# main.net
KiCad netlist of a schematic drawn in EAGLE
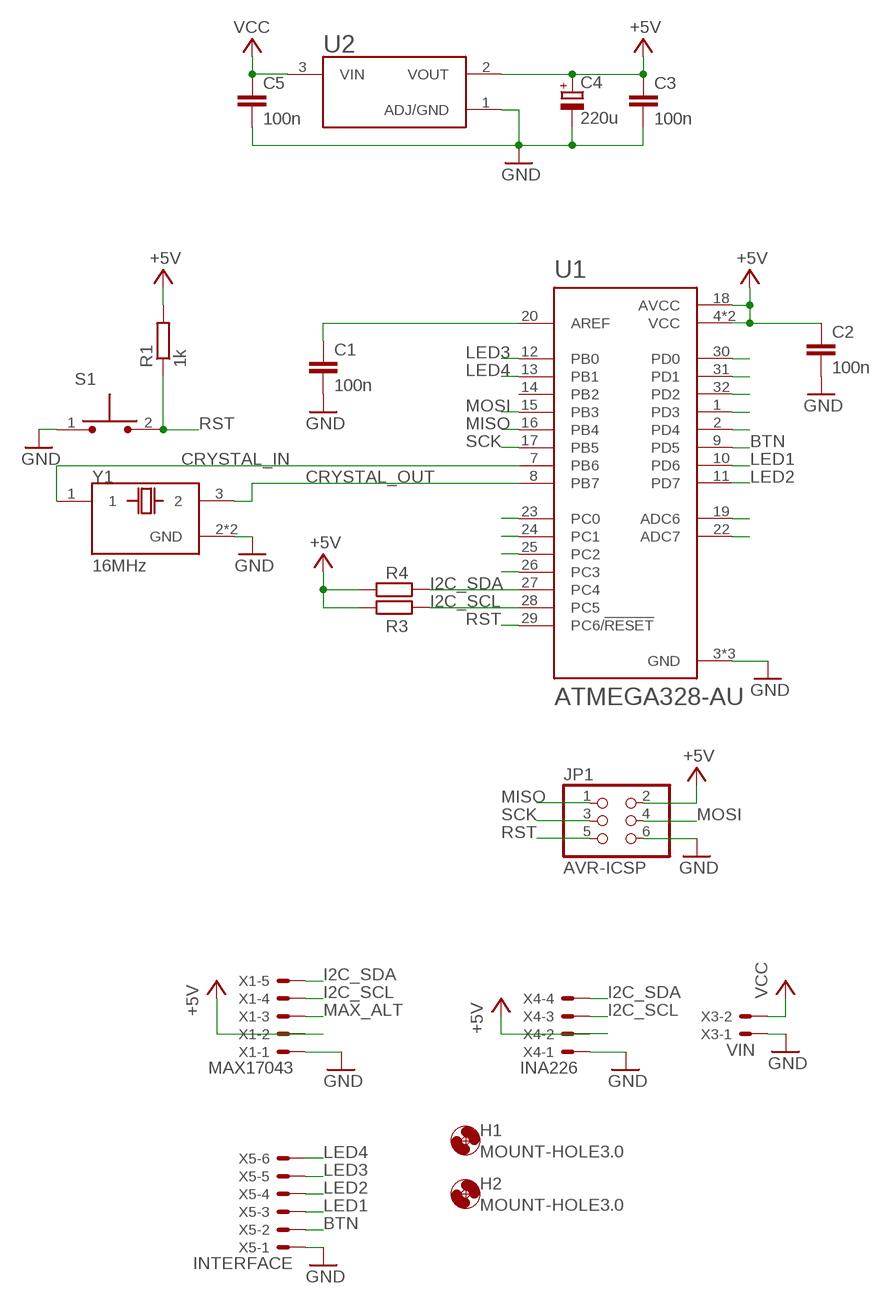
[diagram p0: schematic, sheet 1]

(export (version "E")
  (design (tool "Eeschema 10.0.6"))
  (components
    (comp (ref "C1")
      (value "100n")
      (footprint "eagle-import:C0805")
      (libsource (lib "eagle-import") (part "C-EUC0805"))
    )
    (comp (ref "C2")
      (value "100n")
      (footprint "eagle-import:C0805")
      (libsource (lib "eagle-import") (part "C-EUC0805"))
    )
    (comp (ref "C3")
      (value "100n")
      (footprint "eagle-import:C0805")
      (libsource (lib "eagle-import") (part "C-EUC0805"))
    )
    (comp (ref "C4")
      (value "220u")
      (footprint "eagle-import:153CLV-0605")
      (libsource (lib "eagle-import") (part "CPOL-EU153CLV-0605"))
    )
    (comp (ref "C5")
      (value "100n")
      (footprint "eagle-import:C0805")
      (libsource (lib "eagle-import") (part "C-EUC0805"))
    )
    (comp (ref "H1")
      (value "MOUNT-HOLE3.0")
      (footprint "eagle-import:3,0")
      (libsource (lib "eagle-import") (part "MOUNT-HOLE3.0"))
    )
    (comp (ref "H2")
      (value "MOUNT-HOLE3.0")
      (footprint "eagle-import:3,0")
      (libsource (lib "eagle-import") (part "MOUNT-HOLE3.0"))
    )
    (comp (ref "JP1")
      (value "AVR-ICSP")
      (footprint "eagle-import:2X03")
      (libsource (lib "eagle-import") (part "PINHD-2X3"))
    )
    (comp (ref "R1")
      (value "1k")
      (footprint "eagle-import:R0805")
      (libsource (lib "eagle-import") (part "R-EU_R0805"))
    )
    (comp (ref "R3")
      (value "R-EU_R0805")
      (footprint "eagle-import:R0805")
      (libsource (lib "eagle-import") (part "R-EU_R0805"))
    )
    (comp (ref "R4")
      (value "R-EU_R0805")
      (footprint "eagle-import:R0805")
      (libsource (lib "eagle-import") (part "R-EU_R0805"))
    )
    (comp (ref "S1")
      (value "TL1015AF160QG")
      (footprint "eagle-import:SW_TL1015AF160QG")
      (fields (field (name "MF") "E-Switch"))
      (libsource (lib "eagle-import") (part "TL1015AF160QG"))
    )
    (comp (ref "U1")
      (value "ATMEGA328-AU")
      (footprint "eagle-import:QFP80P900X900X120-32N")
      (fields (field (name "MF") "Microchip"))
      (libsource (lib "eagle-import") (part "ATMEGA328-AU"))
    )
    (comp (ref "U2")
      (value "AMS1117-3.3")
      (footprint "eagle-import:SOT229P700X180-4N")
      (fields (field (name "MF") "Advanced Monolithic Systems"))
      (libsource (lib "eagle-import") (part "AMS1117-3.3"))
    )
    (comp (ref "X1")
      (value "MAX17043")
      (footprint "eagle-import:JST-XH-05-PACKAGE-LONG-PAD")
      (libsource (lib "eagle-import") (part "JST-XH-05-PIN-LONG-PAD"))
    )
    (comp (ref "X3")
      (value "VIN")
      (footprint "eagle-import:JST-XH-02-PACKAGE-LONG-PAD")
      (libsource (lib "eagle-import") (part "JST-XH-02-PIN-LONG-PAD"))
    )
    (comp (ref "X4")
      (value "INA226")
      (footprint "eagle-import:JST-XH-04-PACKAGE-LONG-PAD")
      (libsource (lib "eagle-import") (part "JST-XH-04-PIN-LONG-PAD"))
    )
    (comp (ref "X5")
      (value "INTERFACE")
      (footprint "eagle-import:JST-XH-06-PACKAGE-LONG-PAD")
      (libsource (lib "eagle-import") (part "JST-XH-06-PIN-LONG-PAD"))
    )
    (comp (ref "Y1")
      (value "16MHz")
      (footprint "eagle-import:XTAL_TSX-3225_16.0000MF18X-AC3")
      (fields (field (name "MF") "EPSON") (field (name "MP") "TSX-3225 16.0000MF18X-AC3"))
      (libsource (lib "eagle-import") (part "TSX-3225_16.0000MF18X-AC3"))
    )
  )
  (nets
    (net (code "1") (name "+5V") (class "Default")
      (node (ref "C2") (pin "1") (pinfunction "1_1") (pintype "passive"))
      (node (ref "C3") (pin "1") (pinfunction "1_1") (pintype "passive"))
      (node (ref "C4") (pin "+") (pinfunction "+_+") (pintype "passive"))
      (node (ref "JP1") (pin "2") (pinfunction "2_2") (pintype "passive"))
      (node (ref "R1") (pin "2") (pinfunction "2_2") (pintype "passive"))
      (node (ref "R3") (pin "1") (pinfunction "1_1") (pintype "passive"))
      (node (ref "R4") (pin "1") (pinfunction "1_1") (pintype "passive"))
      (node (ref "U1") (pin "18") (pinfunction "AVCC_18") (pintype "power_in"))
      (node (ref "U1") (pin "4") (pinfunction "VCC_4") (pintype "power_in"))
      (node (ref "U1") (pin "6") (pinfunction "VCC_6") (pintype "power_in"))
      (node (ref "U2") (pin "2") (pinfunction "VOUT_2") (pintype "output"))
      (node (ref "X1") (pin "2") (pinfunction "S_2") (pintype "passive"))
      (node (ref "X4") (pin "2") (pinfunction "S_2") (pintype "passive"))
    )
    (net (code "2") (name "/BTN") (class "Default")
      (node (ref "U1") (pin "9") (pinfunction "PD5_9") (pintype "bidirectional"))
      (node (ref "X5") (pin "2") (pinfunction "S_2") (pintype "passive"))
    )
    (net (code "3") (name "/CRYSTAL_IN") (class "Default")
      (node (ref "U1") (pin "7") (pinfunction "PB6_7") (pintype "bidirectional"))
      (node (ref "Y1") (pin "1") (pinfunction "1_1") (pintype "passive"))
    )
    (net (code "4") (name "/CRYSTAL_OUT") (class "Default")
      (node (ref "U1") (pin "8") (pinfunction "PB7_8") (pintype "bidirectional"))
      (node (ref "Y1") (pin "3") (pinfunction "2_3") (pintype "passive"))
    )
    (net (code "5") (name "/I2C_SCL") (class "Default")
      (node (ref "R3") (pin "2") (pinfunction "2_2") (pintype "passive"))
      (node (ref "U1") (pin "28") (pinfunction "PC5_28") (pintype "bidirectional"))
      (node (ref "X1") (pin "4") (pinfunction "S_4") (pintype "passive"))
      (node (ref "X4") (pin "3") (pinfunction "S_3") (pintype "passive"))
    )
    (net (code "6") (name "/I2C_SDA") (class "Default")
      (node (ref "R4") (pin "2") (pinfunction "2_2") (pintype "passive"))
      (node (ref "U1") (pin "27") (pinfunction "PC4_27") (pintype "bidirectional"))
      (node (ref "X1") (pin "5") (pinfunction "S_5") (pintype "passive"))
      (node (ref "X4") (pin "4") (pinfunction "S_4") (pintype "passive"))
    )
    (net (code "7") (name "/LED1") (class "Default")
      (node (ref "U1") (pin "10") (pinfunction "PD6_10") (pintype "bidirectional"))
      (node (ref "X5") (pin "3") (pinfunction "S_3") (pintype "passive"))
    )
    (net (code "8") (name "/LED2") (class "Default")
      (node (ref "U1") (pin "11") (pinfunction "PD7_11") (pintype "bidirectional"))
      (node (ref "X5") (pin "4") (pinfunction "S_4") (pintype "passive"))
    )
    (net (code "9") (name "/LED3") (class "Default")
      (node (ref "U1") (pin "12") (pinfunction "PB0_12") (pintype "bidirectional"))
      (node (ref "X5") (pin "5") (pinfunction "S_5") (pintype "passive"))
    )
    (net (code "10") (name "/LED4") (class "Default")
      (node (ref "U1") (pin "13") (pinfunction "PB1_13") (pintype "bidirectional"))
      (node (ref "X5") (pin "6") (pinfunction "S_6") (pintype "passive"))
    )
    (net (code "11") (name "/MAX_ALT") (class "Default")
      (node (ref "U1") (pin "32") (pinfunction "PD2_32") (pintype "bidirectional"))
      (node (ref "X1") (pin "3") (pinfunction "S_3") (pintype "passive"))
    )
    (net (code "12") (name "/MISO") (class "Default")
      (node (ref "JP1") (pin "1") (pinfunction "1_1") (pintype "passive"))
      (node (ref "U1") (pin "16") (pinfunction "PB4_16") (pintype "bidirectional"))
    )
    (net (code "13") (name "/MOSI") (class "Default")
      (node (ref "JP1") (pin "4") (pinfunction "4_4") (pintype "passive"))
      (node (ref "U1") (pin "15") (pinfunction "PB3_15") (pintype "bidirectional"))
    )
    (net (code "14") (name "/RST") (class "Default")
      (node (ref "JP1") (pin "5") (pinfunction "5_5") (pintype "passive"))
      (node (ref "R1") (pin "1") (pinfunction "1_1") (pintype "passive"))
      (node (ref "S1") (pin "2") (pinfunction "2_2") (pintype "passive"))
      (node (ref "U1") (pin "29") (pinfunction "PC6/~{RESET}_29") (pintype "bidirectional"))
    )
    (net (code "15") (name "/SCK") (class "Default")
      (node (ref "JP1") (pin "3") (pinfunction "3_3") (pintype "passive"))
      (node (ref "U1") (pin "17") (pinfunction "PB5_17") (pintype "bidirectional"))
    )
    (net (code "16") (name "GND") (class "Default")
      (node (ref "C1") (pin "2") (pinfunction "2_2") (pintype "passive"))
      (node (ref "C2") (pin "2") (pinfunction "2_2") (pintype "passive"))
      (node (ref "C3") (pin "2") (pinfunction "2_2") (pintype "passive"))
      (node (ref "C4") (pin "-") (pinfunction "-_-") (pintype "passive"))
      (node (ref "C5") (pin "2") (pinfunction "2_2") (pintype "passive"))
      (node (ref "JP1") (pin "6") (pinfunction "6_6") (pintype "passive"))
      (node (ref "S1") (pin "1") (pinfunction "1_1") (pintype "passive"))
      (node (ref "U1") (pin "21") (pinfunction "GND_21") (pintype "power_in"))
      (node (ref "U1") (pin "3") (pinfunction "GND_3") (pintype "power_in"))
      (node (ref "U1") (pin "5") (pinfunction "GND_5") (pintype "power_in"))
      (node (ref "U2") (pin "1") (pinfunction "ADJ/GND_1") (pintype "power_in"))
      (node (ref "X1") (pin "1") (pinfunction "S_1") (pintype "passive"))
      (node (ref "X3") (pin "1") (pinfunction "S_1") (pintype "passive"))
      (node (ref "X4") (pin "1") (pinfunction "S_1") (pintype "passive"))
      (node (ref "X5") (pin "1") (pinfunction "S_1") (pintype "passive"))
      (node (ref "Y1") (pin "2") (pinfunction "GND_2") (pintype "power_in"))
      (node (ref "Y1") (pin "4") (pinfunction "GND_4") (pintype "power_in"))
    )
    (net (code "17") (name "Net-(U1-AREF)") (class "Default")
      (node (ref "C1") (pin "1") (pinfunction "1_1") (pintype "passive"))
      (node (ref "U1") (pin "20") (pinfunction "AREF_20") (pintype "input"))
    )
    (net (code "18") (name "VCC") (class "Default")
      (node (ref "C5") (pin "1") (pinfunction "1_1") (pintype "passive"))
      (node (ref "U2") (pin "3") (pinfunction "VIN_3") (pintype "input"))
      (node (ref "X3") (pin "2") (pinfunction "S_2") (pintype "passive"))
    )
    (net (code "19") (name "unconnected-(U1-ADC6-Pad19)") (class "Default")
      (node (ref "U1") (pin "19") (pinfunction "ADC6_19") (pintype "bidirectional"))
    )
    (net (code "20") (name "unconnected-(U1-ADC7-Pad22)") (class "Default")
      (node (ref "U1") (pin "22") (pinfunction "ADC7_22") (pintype "bidirectional"))
    )
    (net (code "21") (name "unconnected-(U1-PB2-Pad14)") (class "Default")
      (node (ref "U1") (pin "14") (pinfunction "PB2_14") (pintype "bidirectional"))
    )
    (net (code "22") (name "unconnected-(U1-PC0-Pad23)") (class "Default")
      (node (ref "U1") (pin "23") (pinfunction "PC0_23") (pintype "bidirectional"))
    )
    (net (code "23") (name "unconnected-(U1-PC1-Pad24)") (class "Default")
      (node (ref "U1") (pin "24") (pinfunction "PC1_24") (pintype "bidirectional"))
    )
    (net (code "24") (name "unconnected-(U1-PC2-Pad25)") (class "Default")
      (node (ref "U1") (pin "25") (pinfunction "PC2_25") (pintype "bidirectional"))
    )
    (net (code "25") (name "unconnected-(U1-PC3-Pad26)") (class "Default")
      (node (ref "U1") (pin "26") (pinfunction "PC3_26") (pintype "bidirectional"))
    )
    (net (code "26") (name "unconnected-(U1-PD0-Pad30)") (class "Default")
      (node (ref "U1") (pin "30") (pinfunction "PD0_30") (pintype "bidirectional"))
    )
    (net (code "27") (name "unconnected-(U1-PD1-Pad31)") (class "Default")
      (node (ref "U1") (pin "31") (pinfunction "PD1_31") (pintype "bidirectional"))
    )
    (net (code "28") (name "unconnected-(U1-PD3-Pad1)") (class "Default")
      (node (ref "U1") (pin "1") (pinfunction "PD3_1") (pintype "bidirectional"))
    )
    (net (code "29") (name "unconnected-(U1-PD4-Pad2)") (class "Default")
      (node (ref "U1") (pin "2") (pinfunction "PD4_2") (pintype "bidirectional"))
    )
  )
)
